# GBZP.net
KiCad netlist of a schematic drawn in EAGLE
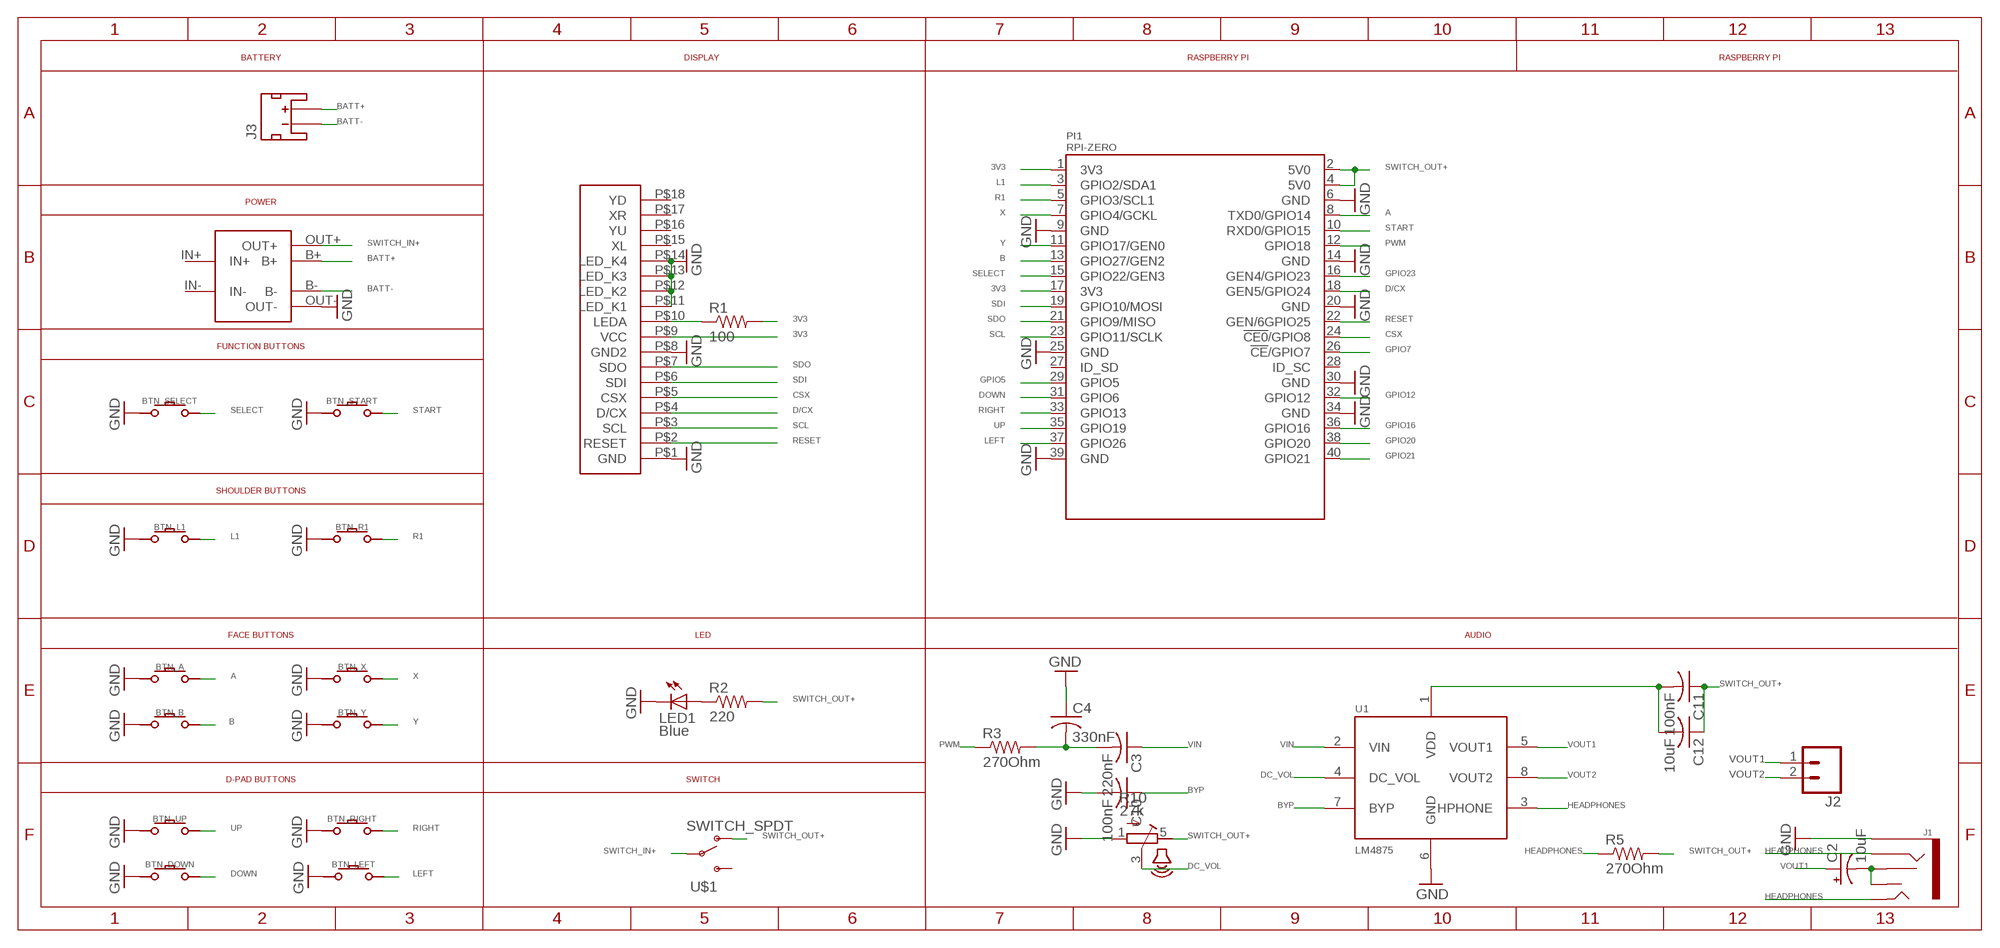
[diagram p0: schematic, sheet 1]

(export (version "E")
  (design (tool "Eeschema 10.0.6"))
  (components
    (comp (ref "BTN_A")
      (value "PAD+SWITCH+HOLE")
      (footprint "eagle-import:PAD+SWITCH+HOLE")
      (libsource (lib "eagle-import") (part "PAD+SWITCH+HOLE"))
    )
    (comp (ref "BTN_B")
      (value "PAD+SWITCH+HOLE")
      (footprint "eagle-import:PAD+SWITCH+HOLE")
      (libsource (lib "eagle-import") (part "PAD+SWITCH+HOLE"))
    )
    (comp (ref "BTN_DOWN")
      (value "PAD+SWITCH+HOLE")
      (footprint "eagle-import:PAD+SWITCH+HOLE")
      (libsource (lib "eagle-import") (part "PAD+SWITCH+HOLE"))
    )
    (comp (ref "BTN_L1")
      (value "PAD+SWITCH+HOLE")
      (footprint "eagle-import:PAD+SWITCH+HOLE")
      (libsource (lib "eagle-import") (part "PAD+SWITCH+HOLE"))
    )
    (comp (ref "BTN_LEFT")
      (value "PAD+SWITCH+HOLE")
      (footprint "eagle-import:PAD+SWITCH+HOLE")
      (libsource (lib "eagle-import") (part "PAD+SWITCH+HOLE"))
    )
    (comp (ref "BTN_R1")
      (value "PAD+SWITCH+HOLE")
      (footprint "eagle-import:PAD+SWITCH+HOLE")
      (libsource (lib "eagle-import") (part "PAD+SWITCH+HOLE"))
    )
    (comp (ref "BTN_RIGHT")
      (value "PAD+SWITCH+HOLE")
      (footprint "eagle-import:PAD+SWITCH+HOLE")
      (libsource (lib "eagle-import") (part "PAD+SWITCH+HOLE"))
    )
    (comp (ref "BTN_SELECT")
      (value "PAD+SWITCH+HOLE")
      (footprint "eagle-import:PAD+SWITCH+HOLE")
      (libsource (lib "eagle-import") (part "PAD+SWITCH+HOLE"))
    )
    (comp (ref "BTN_START")
      (value "PAD+SWITCH+HOLE")
      (footprint "eagle-import:PAD+SWITCH+HOLE")
      (libsource (lib "eagle-import") (part "PAD+SWITCH+HOLE"))
    )
    (comp (ref "BTN_UP")
      (value "PAD+SWITCH+HOLE")
      (footprint "eagle-import:PAD+SWITCH+HOLE")
      (libsource (lib "eagle-import") (part "PAD+SWITCH+HOLE"))
    )
    (comp (ref "BTN_X")
      (value "PAD+SWITCH+HOLE")
      (footprint "eagle-import:PAD+SWITCH+HOLE")
      (libsource (lib "eagle-import") (part "PAD+SWITCH+HOLE"))
    )
    (comp (ref "BTN_Y")
      (value "PAD+SWITCH+HOLE")
      (footprint "eagle-import:PAD+SWITCH+HOLE")
      (libsource (lib "eagle-import") (part "PAD+SWITCH+HOLE"))
    )
    (comp (ref "C2")
      (value "10uF")
      (footprint "eagle-import:EIA3216")
      (libsource (lib "eagle-import") (part "10UF-POLAR-EIA3216-16V-10%(TANT)"))
    )
    (comp (ref "C3")
      (value "220nF")
      (footprint "eagle-import:C0805")
      (libsource (lib "eagle-import") (part "C-USC0805"))
    )
    (comp (ref "C4")
      (value "330nF")
      (footprint "eagle-import:C0805")
      (libsource (lib "eagle-import") (part "C-USC0805"))
    )
    (comp (ref "C10")
      (value "100nF")
      (footprint "eagle-import:C0805")
      (libsource (lib "eagle-import") (part "C-USC0805"))
    )
    (comp (ref "C11")
      (value "100nF")
      (footprint "eagle-import:C0805")
      (libsource (lib "eagle-import") (part "C-USC0805"))
    )
    (comp (ref "C12")
      (value "10uF")
      (footprint "eagle-import:C0805")
      (libsource (lib "eagle-import") (part "C-USC0805"))
    )
    (comp (ref "ILI9341-TFT-2.8")
      (value "GAMEBOYZEROHANDHELDDISPLAYS-2.8")
      (footprint "eagle-import:GAMEBOYZEROHANDHELDDISPLAYS-2.8")
      (libsource (lib "eagle-import") (part "GAMEBOYZEROHANDHELDDISPLAYS-2.8"))
    )
    (comp (ref "J1")
      (value "AUDIO_JACK_3.5MM_PTH")
      (footprint "eagle-import:AUDIO-JACK")
      (libsource (lib "eagle-import") (part "AUDIO_JACK_3.5MM_PTH"))
    )
    (comp (ref "J2")
      (value "CONN_02")
      (footprint "eagle-import:1X02")
      (libsource (lib "eagle-import") (part "CONN_02"))
    )
    (comp (ref "J3")
      (value "JST_2MM_MALE")
      (footprint "eagle-import:JST-2-SMD")
      (libsource (lib "eagle-import") (part "JST_2MM_MALE"))
    )
    (comp (ref "LED1")
      (value "Blue")
      (footprint "eagle-import:CHIPLED_0805")
      (libsource (lib "eagle-import") (part "LEDCHIPLED_0805"))
    )
    (comp (ref "PI1")
      (value "RPI-ZERO")
      (footprint "eagle-import:RASPBERRYPI_BASTELSTUBE_V13_RASPI_BOARD_B+_FULL")
      (libsource (lib "eagle-import") (part "RPI-ZERO"))
    )
    (comp (ref "POWER1")
      (value "03962A")
      (footprint "eagle-import:03962A")
      (libsource (lib "eagle-import") (part "03962A"))
    )
    (comp (ref "R1")
      (value "100")
      (footprint "eagle-import:R0805")
      (libsource (lib "eagle-import") (part "R-US_R0805"))
    )
    (comp (ref "R2")
      (value "220")
      (footprint "eagle-import:R0805")
      (libsource (lib "eagle-import") (part "R-US_R0805"))
    )
    (comp (ref "R3")
      (value "270Ohm")
      (footprint "eagle-import:R0805")
      (libsource (lib "eagle-import") (part "adafruit_420_R-US_R0805"))
    )
    (comp (ref "R5")
      (value "270Ohm")
      (footprint "eagle-import:R0805")
      (libsource (lib "eagle-import") (part "adafruit_420_R-US_R0805"))
    )
    (comp (ref "R10")
      (value "27k")
      (footprint "eagle-import:VOLUME")
      (libsource (lib "eagle-import") (part "VOLUME"))
    )
    (comp (ref "U$1")
      (value "SWITCH_SPDT")
      (footprint "eagle-import:KPS-1290")
      (libsource (lib "eagle-import") (part "SWITCH_SPDT"))
    )
    (comp (ref "U1")
      (value "LM4875")
      (footprint "eagle-import:SOIC8")
      (libsource (lib "eagle-import") (part "LM4875"))
    )
  )
  (nets
    (net (code "1") (name "/3V3") (class "Default")
      (node (ref "ILI9341-TFT-2.8") (pin "P$9") (pinfunction "VCC_P$9") (pintype "bidirectional"))
      (node (ref "PI1") (pin "1") (pinfunction "3V3_1") (pintype "power_in"))
      (node (ref "PI1") (pin "17") (pinfunction "3V3_17") (pintype "power_in"))
      (node (ref "R1") (pin "2") (pinfunction "2_2") (pintype "passive"))
    )
    (net (code "2") (name "/A") (class "Default")
      (node (ref "BTN_A") (pin "P$ACTIVE") (pinfunction "P$ACTIVE_P$ACTIVE") (pintype "bidirectional"))
      (node (ref "PI1") (pin "8") (pinfunction "TXD0/GPIO14_8") (pintype "bidirectional"))
    )
    (net (code "3") (name "/B") (class "Default")
      (node (ref "BTN_B") (pin "P$ACTIVE") (pinfunction "P$ACTIVE_P$ACTIVE") (pintype "bidirectional"))
      (node (ref "PI1") (pin "13") (pinfunction "GPIO27/GEN2_13") (pintype "bidirectional"))
    )
    (net (code "4") (name "/BATT+") (class "Default")
      (node (ref "J3") (pin "2") (pinfunction "+_2") (pintype "bidirectional"))
      (node (ref "POWER1") (pin "B+") (pinfunction "B+_B+") (pintype "bidirectional"))
    )
    (net (code "5") (name "/BATT-") (class "Default")
      (node (ref "J3") (pin "1") (pinfunction "-_1") (pintype "bidirectional"))
      (node (ref "POWER1") (pin "B-") (pinfunction "B-_B-") (pintype "bidirectional"))
    )
    (net (code "6") (name "/BYP") (class "Default")
      (node (ref "C10") (pin "1") (pinfunction "1_1") (pintype "passive"))
      (node (ref "U1") (pin "7") (pinfunction "BYP_7") (pintype "bidirectional"))
    )
    (net (code "7") (name "/CSX") (class "Default")
      (node (ref "ILI9341-TFT-2.8") (pin "P$5") (pinfunction "CSX_P$5") (pintype "bidirectional"))
      (node (ref "PI1") (pin "24") (pinfunction "~{CE0}/GPIO8_24") (pintype "bidirectional"))
    )
    (net (code "8") (name "/DC_VOL") (class "Default")
      (node (ref "R10") (pin "3") (pinfunction "S_3") (pintype "passive"))
      (node (ref "U1") (pin "4") (pinfunction "DC_VOL_4") (pintype "input"))
    )
    (net (code "9") (name "/DOWN") (class "Default")
      (node (ref "BTN_DOWN") (pin "P$ACTIVE") (pinfunction "P$ACTIVE_P$ACTIVE") (pintype "bidirectional"))
      (node (ref "PI1") (pin "31") (pinfunction "GPIO6_31") (pintype "bidirectional"))
    )
    (net (code "10") (name "/D{slash}CX") (class "Default")
      (node (ref "ILI9341-TFT-2.8") (pin "P$4") (pinfunction "D/CX_P$4") (pintype "bidirectional"))
      (node (ref "PI1") (pin "18") (pinfunction "GEN5/GPIO24_18") (pintype "bidirectional"))
    )
    (net (code "11") (name "/GPIO5") (class "Default")
      (node (ref "PI1") (pin "29") (pinfunction "GPIO5_29") (pintype "bidirectional"))
    )
    (net (code "12") (name "/GPIO7") (class "Default")
      (node (ref "PI1") (pin "26") (pinfunction "~{CE}/GPIO7_26") (pintype "bidirectional"))
    )
    (net (code "13") (name "/GPIO12") (class "Default")
      (node (ref "PI1") (pin "32") (pinfunction "GPIO12_32") (pintype "bidirectional"))
    )
    (net (code "14") (name "/GPIO16") (class "Default")
      (node (ref "PI1") (pin "36") (pinfunction "GPIO16_36") (pintype "bidirectional"))
    )
    (net (code "15") (name "/GPIO20") (class "Default")
      (node (ref "PI1") (pin "38") (pinfunction "GPIO20_38") (pintype "bidirectional"))
    )
    (net (code "16") (name "/GPIO21") (class "Default")
      (node (ref "PI1") (pin "40") (pinfunction "GPIO21_40") (pintype "bidirectional"))
    )
    (net (code "17") (name "/GPIO23") (class "Default")
      (node (ref "PI1") (pin "16") (pinfunction "GEN4/GPIO23_16") (pintype "bidirectional"))
    )
    (net (code "18") (name "/HEADPHONES") (class "Default")
      (node (ref "J1") (pin "RING") (pinfunction "RING_RING") (pintype "bidirectional"))
      (node (ref "J1") (pin "TIP") (pinfunction "TIP_TIP") (pintype "bidirectional"))
      (node (ref "R5") (pin "1") (pinfunction "1_1") (pintype "passive"))
      (node (ref "U1") (pin "3") (pinfunction "HPHONE_3") (pintype "input"))
    )
    (net (code "19") (name "/L1") (class "Default")
      (node (ref "BTN_L1") (pin "P$ACTIVE") (pinfunction "P$ACTIVE_P$ACTIVE") (pintype "bidirectional"))
      (node (ref "PI1") (pin "3") (pinfunction "GPIO2/SDA1_3") (pintype "bidirectional"))
    )
    (net (code "20") (name "/LEFT") (class "Default")
      (node (ref "BTN_LEFT") (pin "P$ACTIVE") (pinfunction "P$ACTIVE_P$ACTIVE") (pintype "bidirectional"))
      (node (ref "PI1") (pin "37") (pinfunction "GPIO26_37") (pintype "bidirectional"))
    )
    (net (code "21") (name "/PWM") (class "Default")
      (node (ref "PI1") (pin "12") (pinfunction "GPIO18_12") (pintype "bidirectional"))
      (node (ref "R3") (pin "1") (pinfunction "1_1") (pintype "passive"))
    )
    (net (code "22") (name "/R1") (class "Default")
      (node (ref "BTN_R1") (pin "P$ACTIVE") (pinfunction "P$ACTIVE_P$ACTIVE") (pintype "bidirectional"))
      (node (ref "PI1") (pin "5") (pinfunction "GPIO3/SCL1_5") (pintype "bidirectional"))
    )
    (net (code "23") (name "/RESET") (class "Default")
      (node (ref "ILI9341-TFT-2.8") (pin "P$2") (pinfunction "RESET_P$2") (pintype "bidirectional"))
      (node (ref "PI1") (pin "22") (pinfunction "GEN/6GPIO25_22") (pintype "bidirectional"))
    )
    (net (code "24") (name "/RIGHT") (class "Default")
      (node (ref "BTN_RIGHT") (pin "P$ACTIVE") (pinfunction "P$ACTIVE_P$ACTIVE") (pintype "bidirectional"))
      (node (ref "PI1") (pin "33") (pinfunction "GPIO13_33") (pintype "bidirectional"))
    )
    (net (code "25") (name "/SCL") (class "Default")
      (node (ref "ILI9341-TFT-2.8") (pin "P$3") (pinfunction "SCL_P$3") (pintype "bidirectional"))
      (node (ref "PI1") (pin "23") (pinfunction "GPIO11/SCLK_23") (pintype "bidirectional"))
    )
    (net (code "26") (name "/SDI") (class "Default")
      (node (ref "ILI9341-TFT-2.8") (pin "P$6") (pinfunction "SDI_P$6") (pintype "bidirectional"))
      (node (ref "PI1") (pin "19") (pinfunction "GPIO10/MOSI_19") (pintype "bidirectional"))
    )
    (net (code "27") (name "/SDO") (class "Default")
      (node (ref "ILI9341-TFT-2.8") (pin "P$7") (pinfunction "SDO_P$7") (pintype "bidirectional"))
      (node (ref "PI1") (pin "21") (pinfunction "GPIO9/MISO_21") (pintype "bidirectional"))
    )
    (net (code "28") (name "/SELECT") (class "Default")
      (node (ref "BTN_SELECT") (pin "P$ACTIVE") (pinfunction "P$ACTIVE_P$ACTIVE") (pintype "bidirectional"))
      (node (ref "PI1") (pin "15") (pinfunction "GPIO22/GEN3_15") (pintype "bidirectional"))
    )
    (net (code "29") (name "/START") (class "Default")
      (node (ref "BTN_START") (pin "P$ACTIVE") (pinfunction "P$ACTIVE_P$ACTIVE") (pintype "bidirectional"))
      (node (ref "PI1") (pin "10") (pinfunction "RXD0/GPIO15_10") (pintype "bidirectional"))
    )
    (net (code "30") (name "/SWITCH_IN+") (class "Default")
      (node (ref "POWER1") (pin "OUT+") (pinfunction "OUT+_OUT+") (pintype "bidirectional"))
      (node (ref "U$1") (pin "P") (pinfunction "P_P") (pintype "passive"))
    )
    (net (code "31") (name "/SWITCH_OUT+") (class "Default")
      (node (ref "C11") (pin "1") (pinfunction "1_1") (pintype "passive"))
      (node (ref "C12") (pin "1") (pinfunction "1_1") (pintype "passive"))
      (node (ref "PI1") (pin "2") (pinfunction "5V0_2") (pintype "power_in"))
      (node (ref "PI1") (pin "4") (pinfunction "5V0_4") (pintype "power_in"))
      (node (ref "R10") (pin "5") (pinfunction "E_5") (pintype "passive"))
      (node (ref "R2") (pin "2") (pinfunction "2_2") (pintype "passive"))
      (node (ref "R5") (pin "2") (pinfunction "2_2") (pintype "passive"))
      (node (ref "U$1") (pin "O") (pinfunction "O_O") (pintype "passive"))
    )
    (net (code "32") (name "/UP") (class "Default")
      (node (ref "BTN_UP") (pin "P$ACTIVE") (pinfunction "P$ACTIVE_P$ACTIVE") (pintype "bidirectional"))
      (node (ref "PI1") (pin "35") (pinfunction "GPIO19_35") (pintype "bidirectional"))
    )
    (net (code "33") (name "/VIN") (class "Default")
      (node (ref "C3") (pin "1") (pinfunction "1_1") (pintype "passive"))
      (node (ref "U1") (pin "2") (pinfunction "VIN_2") (pintype "input"))
    )
    (net (code "34") (name "/VOUT1") (class "Default")
      (node (ref "C2") (pin "+") (pinfunction "+_+") (pintype "passive"))
      (node (ref "J2") (pin "1") (pinfunction "1_1") (pintype "passive"))
      (node (ref "U1") (pin "5") (pinfunction "VOUT1_5") (pintype "output"))
    )
    (net (code "35") (name "/VOUT2") (class "Default")
      (node (ref "J2") (pin "2") (pinfunction "2_2") (pintype "passive"))
      (node (ref "U1") (pin "8") (pinfunction "VOUT2_8") (pintype "output"))
    )
    (net (code "36") (name "/X") (class "Default")
      (node (ref "BTN_X") (pin "P$ACTIVE") (pinfunction "P$ACTIVE_P$ACTIVE") (pintype "bidirectional"))
      (node (ref "PI1") (pin "7") (pinfunction "GPIO4/GCKL_7") (pintype "bidirectional"))
    )
    (net (code "37") (name "/Y") (class "Default")
      (node (ref "BTN_Y") (pin "P$ACTIVE") (pinfunction "P$ACTIVE_P$ACTIVE") (pintype "bidirectional"))
      (node (ref "PI1") (pin "11") (pinfunction "GPIO17/GEN0_11") (pintype "bidirectional"))
    )
    (net (code "38") (name "GND") (class "Default")
      (node (ref "BTN_A") (pin "P$GND") (pinfunction "P$GND_P$GND") (pintype "bidirectional"))
      (node (ref "BTN_B") (pin "P$GND") (pinfunction "P$GND_P$GND") (pintype "bidirectional"))
      (node (ref "BTN_DOWN") (pin "P$GND") (pinfunction "P$GND_P$GND") (pintype "bidirectional"))
      (node (ref "BTN_L1") (pin "P$GND") (pinfunction "P$GND_P$GND") (pintype "bidirectional"))
      (node (ref "BTN_LEFT") (pin "P$GND") (pinfunction "P$GND_P$GND") (pintype "bidirectional"))
      (node (ref "BTN_R1") (pin "P$GND") (pinfunction "P$GND_P$GND") (pintype "bidirectional"))
      (node (ref "BTN_RIGHT") (pin "P$GND") (pinfunction "P$GND_P$GND") (pintype "bidirectional"))
      (node (ref "BTN_SELECT") (pin "P$GND") (pinfunction "P$GND_P$GND") (pintype "bidirectional"))
      (node (ref "BTN_START") (pin "P$GND") (pinfunction "P$GND_P$GND") (pintype "bidirectional"))
      (node (ref "BTN_UP") (pin "P$GND") (pinfunction "P$GND_P$GND") (pintype "bidirectional"))
      (node (ref "BTN_X") (pin "P$GND") (pinfunction "P$GND_P$GND") (pintype "bidirectional"))
      (node (ref "BTN_Y") (pin "P$GND") (pinfunction "P$GND_P$GND") (pintype "bidirectional"))
      (node (ref "C10") (pin "2") (pinfunction "2_2") (pintype "passive"))
      (node (ref "C4") (pin "1") (pinfunction "1_1") (pintype "passive"))
      (node (ref "ILI9341-TFT-2.8") (pin "P$1") (pinfunction "GND_P$1") (pintype "bidirectional"))
      (node (ref "ILI9341-TFT-2.8") (pin "P$11") (pinfunction "LED_K1_P$11") (pintype "bidirectional"))
      (node (ref "ILI9341-TFT-2.8") (pin "P$12") (pinfunction "LED_K2_P$12") (pintype "bidirectional"))
      (node (ref "ILI9341-TFT-2.8") (pin "P$13") (pinfunction "LED_K3_P$13") (pintype "bidirectional"))
      (node (ref "ILI9341-TFT-2.8") (pin "P$14") (pinfunction "LED_K4_P$14") (pintype "bidirectional"))
      (node (ref "ILI9341-TFT-2.8") (pin "P$8") (pinfunction "GND2_P$8") (pintype "bidirectional"))
      (node (ref "J1") (pin "SLEEVE") (pinfunction "SLEEVE_SLEEVE") (pintype "bidirectional"))
      (node (ref "LED1") (pin "C") (pinfunction "C_C") (pintype "passive"))
      (node (ref "PI1") (pin "14") (pinfunction "GND_14") (pintype "power_in"))
      (node (ref "PI1") (pin "20") (pinfunction "GND_20") (pintype "power_in"))
      (node (ref "PI1") (pin "25") (pinfunction "GND_25") (pintype "power_in"))
      (node (ref "PI1") (pin "30") (pinfunction "GND_30") (pintype "power_in"))
      (node (ref "PI1") (pin "34") (pinfunction "GND_34") (pintype "power_in"))
      (node (ref "PI1") (pin "39") (pinfunction "GND_39") (pintype "power_in"))
      (node (ref "PI1") (pin "6") (pinfunction "GND_6") (pintype "power_in"))
      (node (ref "PI1") (pin "9") (pinfunction "GND_9") (pintype "power_in"))
      (node (ref "POWER1") (pin "OUT-") (pinfunction "OUT-_OUT-") (pintype "bidirectional"))
      (node (ref "R10") (pin "1") (pinfunction "A_1") (pintype "passive"))
      (node (ref "U1") (pin "6") (pinfunction "GND_6") (pintype "power_in"))
    )
    (net (code "39") (name "Net-(C2-Pad-)") (class "Default")
      (node (ref "C2") (pin "-") (pinfunction "-_-") (pintype "passive"))
      (node (ref "J1") (pin "RSH") (pinfunction "RSH_RSH") (pintype "bidirectional"))
      (node (ref "J1") (pin "TSH") (pinfunction "TSH_TSH") (pintype "bidirectional"))
    )
    (net (code "40") (name "Net-(C3-Pad2)") (class "Default")
      (node (ref "C3") (pin "2") (pinfunction "2_2") (pintype "passive"))
      (node (ref "C4") (pin "2") (pinfunction "2_2") (pintype "passive"))
      (node (ref "R3") (pin "2") (pinfunction "2_2") (pintype "passive"))
    )
    (net (code "41") (name "Net-(ILI9341-TFT-2.8-LEDA)") (class "Default")
      (node (ref "ILI9341-TFT-2.8") (pin "P$10") (pinfunction "LEDA_P$10") (pintype "bidirectional"))
      (node (ref "R1") (pin "1") (pinfunction "1_1") (pintype "passive"))
    )
    (net (code "42") (name "Net-(LED1-PadA)") (class "Default")
      (node (ref "LED1") (pin "A") (pinfunction "A_A") (pintype "passive"))
      (node (ref "R2") (pin "1") (pinfunction "1_1") (pintype "passive"))
    )
    (net (code "43") (name "Net-(U1-VDD)") (class "Default")
      (node (ref "C11") (pin "2") (pinfunction "2_2") (pintype "passive"))
      (node (ref "C12") (pin "2") (pinfunction "2_2") (pintype "passive"))
      (node (ref "U1") (pin "1") (pinfunction "VDD_1") (pintype "power_in"))
    )
    (net (code "44") (name "unconnected-(ILI9341-TFT-2.8-XL-PadP$15)") (class "Default")
      (node (ref "ILI9341-TFT-2.8") (pin "P$15") (pinfunction "XL_P$15") (pintype "bidirectional"))
    )
    (net (code "45") (name "unconnected-(ILI9341-TFT-2.8-XR-PadP$17)") (class "Default")
      (node (ref "ILI9341-TFT-2.8") (pin "P$17") (pinfunction "XR_P$17") (pintype "bidirectional"))
    )
    (net (code "46") (name "unconnected-(ILI9341-TFT-2.8-YD-PadP$18)") (class "Default")
      (node (ref "ILI9341-TFT-2.8") (pin "P$18") (pinfunction "YD_P$18") (pintype "bidirectional"))
    )
    (net (code "47") (name "unconnected-(ILI9341-TFT-2.8-YU-PadP$16)") (class "Default")
      (node (ref "ILI9341-TFT-2.8") (pin "P$16") (pinfunction "YU_P$16") (pintype "bidirectional"))
    )
    (net (code "48") (name "unconnected-(J3-PAD1-PadNC1)") (class "Default")
      (node (ref "J3") (pin "NC1") (pinfunction "PAD1_NC1") (pintype "bidirectional"))
    )
    (net (code "49") (name "unconnected-(J3-PAD2-PadNC2)") (class "Default")
      (node (ref "J3") (pin "NC2") (pinfunction "PAD2_NC2") (pintype "bidirectional"))
    )
    (net (code "50") (name "unconnected-(PI1-ID_SC-Pad28)") (class "Default")
      (node (ref "PI1") (pin "28") (pinfunction "ID_SC_28") (pintype "bidirectional"))
    )
    (net (code "51") (name "unconnected-(PI1-ID_SD-Pad27)") (class "Default")
      (node (ref "PI1") (pin "27") (pinfunction "ID_SD_27") (pintype "bidirectional"))
    )
    (net (code "52") (name "unconnected-(POWER1-PadIN+)") (class "Default")
      (node (ref "POWER1") (pin "IN+") (pinfunction "IN+_IN+") (pintype "bidirectional"))
    )
    (net (code "53") (name "unconnected-(POWER1-PadIN-)") (class "Default")
      (node (ref "POWER1") (pin "IN-") (pinfunction "IN-_IN-") (pintype "bidirectional"))
    )
    (net (code "54") (name "unconnected-(U$1-PadS)") (class "Default")
      (node (ref "U$1") (pin "S") (pinfunction "S_S") (pintype "passive"))
    )
  )
)
